# dsky_md_4_01v.net
KiCad netlist of a schematic drawn in EAGLE
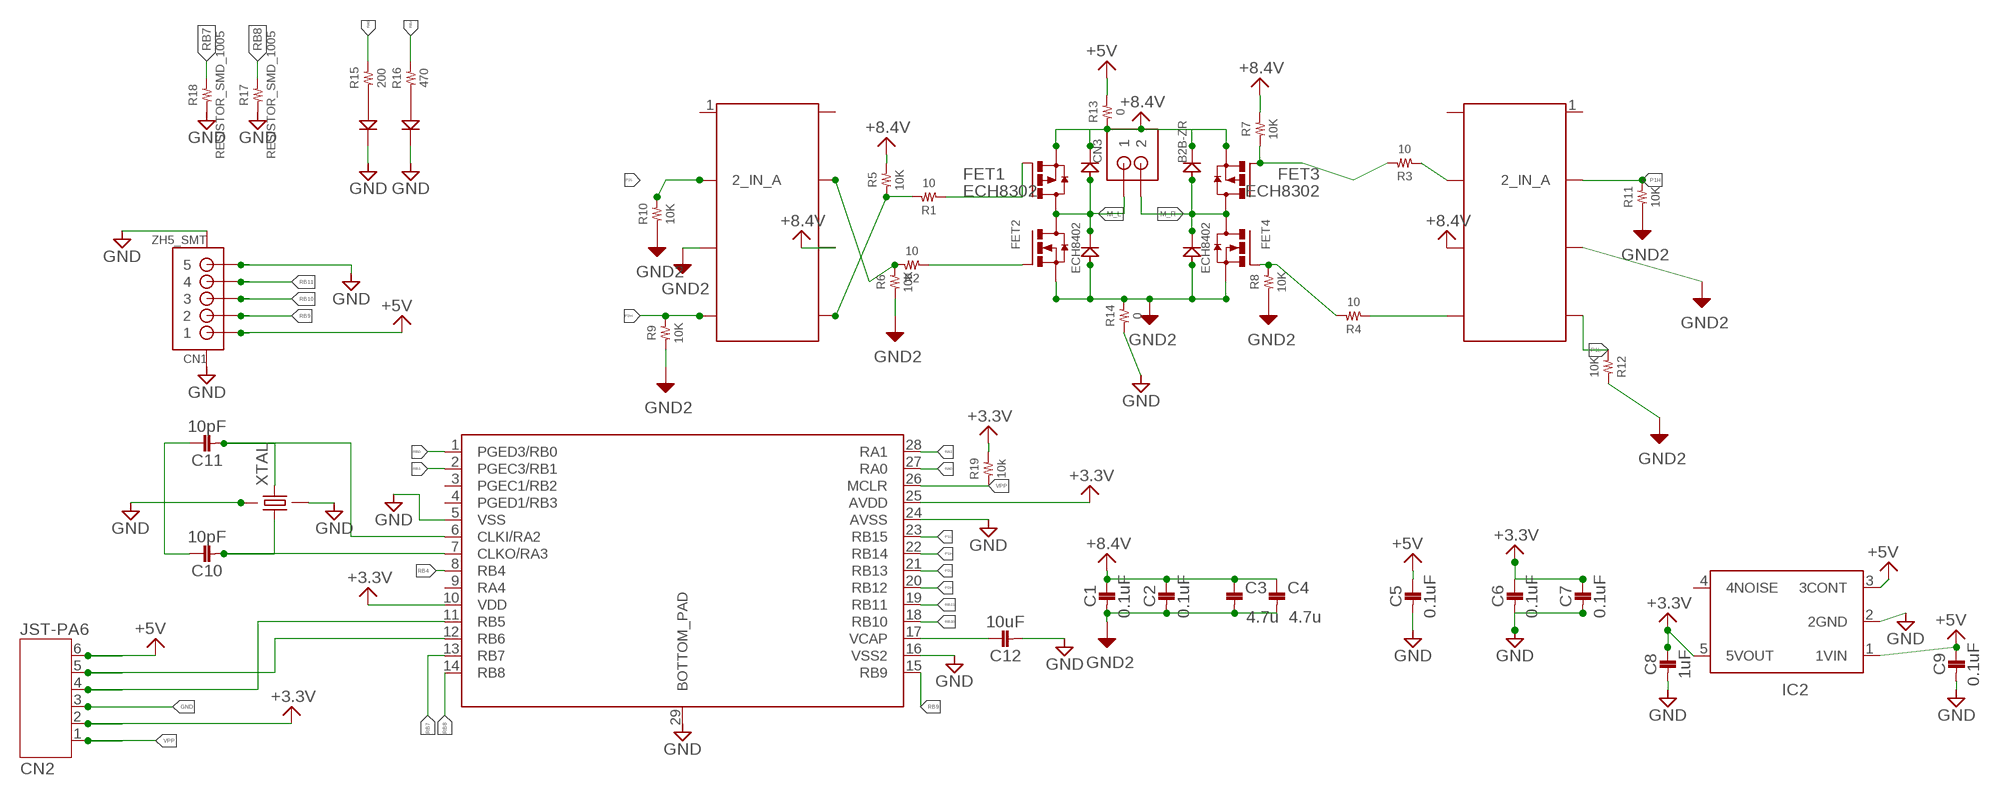
[diagram p0: schematic, sheet 1]

(export (version "E")
  (design (tool "Eeschema 10.0.6"))
  (components
    (comp (ref "C1")
      (value "0.1uF")
      (footprint "eagle-import:1608")
      (libsource (lib "eagle-import") (part "1608"))
    )
    (comp (ref "C2")
      (value "0.1uF")
      (footprint "eagle-import:1608")
      (libsource (lib "eagle-import") (part "1608"))
    )
    (comp (ref "C3")
      (value "4.7u")
      (footprint "eagle-import:2012")
      (libsource (lib "eagle-import") (part "2012"))
    )
    (comp (ref "C4")
      (value "4.7u")
      (footprint "eagle-import:2012")
      (libsource (lib "eagle-import") (part "2012"))
    )
    (comp (ref "C5")
      (value "0.1uF")
      (footprint "eagle-import:1608")
      (libsource (lib "eagle-import") (part "1608"))
    )
    (comp (ref "C6")
      (value "0.1uF")
      (footprint "eagle-import:1608")
      (libsource (lib "eagle-import") (part "1608"))
    )
    (comp (ref "C7")
      (value "0.1uF")
      (footprint "eagle-import:1608")
      (libsource (lib "eagle-import") (part "1608"))
    )
    (comp (ref "C8")
      (value "1uF")
      (footprint "eagle-import:1608")
      (libsource (lib "eagle-import") (part "1608"))
    )
    (comp (ref "C9")
      (value "0.1uF")
      (footprint "eagle-import:1608")
      (libsource (lib "eagle-import") (part "1608"))
    )
    (comp (ref "C10")
      (value "10pF")
      (footprint "eagle-import:1608")
      (libsource (lib "eagle-import") (part "1608"))
    )
    (comp (ref "C11")
      (value "10pF")
      (footprint "eagle-import:1608")
      (libsource (lib "eagle-import") (part "1608"))
    )
    (comp (ref "C12")
      (value "10uF")
      (footprint "eagle-import:1608")
      (libsource (lib "eagle-import") (part "1608"))
    )
    (comp (ref "CN1")
      (value "ZH5_SMT")
      (footprint "eagle-import:ZH5_SMT")
      (libsource (lib "eagle-import") (part "ZH5_SMT"))
    )
    (comp (ref "CN2")
      (value "JST-PA6")
      (footprint "eagle-import:JST-PA6")
      (libsource (lib "eagle-import") (part "JST-PA6"))
    )
    (comp (ref "CN3")
      (value "B2B-ZR")
      (footprint "eagle-import:B2B-ZR")
      (libsource (lib "eagle-import") (part "B2B-ZR"))
    )
    (comp (ref "D1")
      (value "SS2040")
      (footprint "eagle-import:SOD-123FL")
      (libsource (lib "eagle-import") (part "SS2040"))
    )
    (comp (ref "D2")
      (value "SS2040")
      (footprint "eagle-import:SOD-123FL")
      (libsource (lib "eagle-import") (part "SS2040"))
    )
    (comp (ref "D3")
      (value "SS2040")
      (footprint "eagle-import:SOD-123FL")
      (libsource (lib "eagle-import") (part "SS2040"))
    )
    (comp (ref "D4")
      (value "SS2040")
      (footprint "eagle-import:SOD-123FL")
      (libsource (lib "eagle-import") (part "SS2040"))
    )
    (comp (ref "FET1")
      (value "ECH8302")
      (footprint "eagle-import:ECH8")
      (libsource (lib "eagle-import") (part "ECH83"))
    )
    (comp (ref "FET2")
      (value "ECH8402")
      (footprint "eagle-import:ECH8")
      (libsource (lib "eagle-import") (part "ECH84"))
    )
    (comp (ref "FET3")
      (value "ECH8302")
      (footprint "eagle-import:ECH8")
      (libsource (lib "eagle-import") (part "ECH83"))
    )
    (comp (ref "FET4")
      (value "ECH8402")
      (footprint "eagle-import:ECH8")
      (libsource (lib "eagle-import") (part "ECH84"))
    )
    (comp (ref "IC1")
      (value "DSPIC33EP32MC202")
      (footprint "eagle-import:QFN-S28_6X6MC")
      (libsource (lib "eagle-import") (part "DSPIC33EP32MC202"))
    )
    (comp (ref "IC2")
      (value "NJM2866F33")
      (footprint "eagle-import:SSOP5-P-0.95")
      (libsource (lib "eagle-import") (part "TAR5SB"))
    )
    (comp (ref "IC3")
      (value "TC1427COA")
      (footprint "eagle-import:SOIC8")
      (libsource (lib "eagle-import") (part "TC1427COA"))
    )
    (comp (ref "IC4")
      (value "TC1427COA")
      (footprint "eagle-import:SOIC8")
      (libsource (lib "eagle-import") (part "TC1427COA"))
    )
    (comp (ref "LED1")
      (value "1608")
      (footprint "eagle-import:1608")
      (libsource (lib "eagle-import") (part "10_LED_1608"))
    )
    (comp (ref "LED2")
      (value "1608")
      (footprint "eagle-import:1608")
      (libsource (lib "eagle-import") (part "10_LED_1608"))
    )
    (comp (ref "R1")
      (value "10")
      (footprint "eagle-import:1608")
      (libsource (lib "eagle-import") (part "RESISTOR__SMD"))
    )
    (comp (ref "R2")
      (value "10")
      (footprint "eagle-import:1608")
      (libsource (lib "eagle-import") (part "RESISTOR__SMD"))
    )
    (comp (ref "R3")
      (value "10")
      (footprint "eagle-import:1608")
      (libsource (lib "eagle-import") (part "RESISTOR__SMD"))
    )
    (comp (ref "R4")
      (value "10")
      (footprint "eagle-import:1608")
      (libsource (lib "eagle-import") (part "RESISTOR__SMD"))
    )
    (comp (ref "R5")
      (value "10K")
      (footprint "eagle-import:1608")
      (libsource (lib "eagle-import") (part "RESISTOR__SMD"))
    )
    (comp (ref "R6")
      (value "10K")
      (footprint "eagle-import:1608")
      (libsource (lib "eagle-import") (part "RESISTOR__SMD"))
    )
    (comp (ref "R7")
      (value "10K")
      (footprint "eagle-import:1608")
      (libsource (lib "eagle-import") (part "RESISTOR__SMD"))
    )
    (comp (ref "R8")
      (value "10K")
      (footprint "eagle-import:1608")
      (libsource (lib "eagle-import") (part "RESISTOR__SMD"))
    )
    (comp (ref "R9")
      (value "10K")
      (footprint "eagle-import:1608")
      (libsource (lib "eagle-import") (part "RESISTOR__SMD"))
    )
    (comp (ref "R10")
      (value "10K")
      (footprint "eagle-import:1608")
      (libsource (lib "eagle-import") (part "RESISTOR__SMD"))
    )
    (comp (ref "R11")
      (value "10K")
      (footprint "eagle-import:1608")
      (libsource (lib "eagle-import") (part "RESISTOR__SMD"))
    )
    (comp (ref "R12")
      (value "10K")
      (footprint "eagle-import:1608")
      (libsource (lib "eagle-import") (part "RESISTOR__SMD"))
    )
    (comp (ref "R13")
      (value "0")
      (footprint "eagle-import:1608")
      (libsource (lib "eagle-import") (part "RESISTOR__SMD"))
    )
    (comp (ref "R14")
      (value "0")
      (footprint "eagle-import:1608")
      (libsource (lib "eagle-import") (part "RESISTOR__SMD"))
    )
    (comp (ref "R15")
      (value "200")
      (footprint "eagle-import:1608")
      (libsource (lib "eagle-import") (part "RESISTOR__SMD"))
    )
    (comp (ref "R16")
      (value "470")
      (footprint "eagle-import:1608")
      (libsource (lib "eagle-import") (part "RESISTOR__SMD"))
    )
    (comp (ref "R17")
      (value "RESISTOR_SMD_1005")
      (footprint "eagle-import:1005")
      (libsource (lib "eagle-import") (part "RESISTOR_SMD_1005"))
    )
    (comp (ref "R18")
      (value "RESISTOR_SMD_1005")
      (footprint "eagle-import:1005")
      (libsource (lib "eagle-import") (part "RESISTOR_SMD_1005"))
    )
    (comp (ref "R19")
      (value "10k")
      (footprint "eagle-import:1608")
      (libsource (lib "eagle-import") (part "RESISTOR__SMD"))
    )
    (comp (ref "XTAL")
      (value "X22")
      (footprint "eagle-import:SMD_X22")
      (libsource (lib "eagle-import") (part "X22"))
    )
  )
  (nets
    (net (code "1") (name "+3.3V") (class "Default")
      (node (ref "C6") (pin "P$1") (pinfunction "1_P$1") (pintype "passive"))
      (node (ref "C7") (pin "P$1") (pinfunction "1_P$1") (pintype "passive"))
      (node (ref "C8") (pin "P$1") (pinfunction "1_P$1") (pintype "passive"))
      (node (ref "CN2") (pin "2") (pinfunction "2_2") (pintype "passive"))
      (node (ref "IC1") (pin "10") (pinfunction "VDD_10") (pintype "bidirectional"))
      (node (ref "IC1") (pin "25") (pinfunction "AVDD_25") (pintype "bidirectional"))
      (node (ref "IC2") (pin "5") (pinfunction "5VOUT_5") (pintype "bidirectional"))
      (node (ref "R19") (pin "2") (pinfunction "P$2_2") (pintype "passive"))
    )
    (net (code "2") (name "+5V") (class "Default")
      (node (ref "C5") (pin "P$1") (pinfunction "1_P$1") (pintype "passive"))
      (node (ref "C9") (pin "P$1") (pinfunction "1_P$1") (pintype "passive"))
      (node (ref "CN1") (pin "P1") (pinfunction "1_P1") (pintype "bidirectional"))
      (node (ref "CN2") (pin "6") (pinfunction "6_6") (pintype "passive"))
      (node (ref "IC2") (pin "1") (pinfunction "1VIN_1") (pintype "bidirectional"))
      (node (ref "IC2") (pin "3") (pinfunction "3CONT_3") (pintype "bidirectional"))
      (node (ref "R13") (pin "2") (pinfunction "P$2_2") (pintype "passive"))
    )
    (net (code "3") (name "+8.4V") (class "Default")
      (node (ref "C1") (pin "P$1") (pinfunction "1_P$1") (pintype "passive"))
      (node (ref "C2") (pin "P$1") (pinfunction "1_P$1") (pintype "passive"))
      (node (ref "C3") (pin "1") (pinfunction "1_1") (pintype "passive"))
      (node (ref "C4") (pin "1") (pinfunction "1_1") (pintype "passive"))
      (node (ref "D1") (pin "2") (pinfunction "PK_2") (pintype "bidirectional"))
      (node (ref "D3") (pin "2") (pinfunction "PK_2") (pintype "bidirectional"))
      (node (ref "FET1") (pin "1") (pinfunction "S_1") (pintype "passive"))
      (node (ref "FET1") (pin "2") (pinfunction "S_2") (pintype "passive"))
      (node (ref "FET1") (pin "3") (pinfunction "S_3") (pintype "passive"))
      (node (ref "FET3") (pin "1") (pinfunction "S_1") (pintype "passive"))
      (node (ref "FET3") (pin "2") (pinfunction "S_2") (pintype "passive"))
      (node (ref "FET3") (pin "3") (pinfunction "S_3") (pintype "passive"))
      (node (ref "IC3") (pin "6") (pinfunction "6_VDD_6") (pintype "bidirectional"))
      (node (ref "IC4") (pin "6") (pinfunction "6_VDD_6") (pintype "bidirectional"))
      (node (ref "R13") (pin "1") (pinfunction "P$1_1") (pintype "passive"))
      (node (ref "R5") (pin "2") (pinfunction "P$2_2") (pintype "passive"))
      (node (ref "R7") (pin "2") (pinfunction "P$2_2") (pintype "passive"))
    )
    (net (code "4") (name "GND") (class "Default")
      (node (ref "C10") (pin "P$1") (pinfunction "1_P$1") (pintype "passive"))
      (node (ref "C11") (pin "P$1") (pinfunction "1_P$1") (pintype "passive"))
      (node (ref "C12") (pin "P$2") (pinfunction "2_P$2") (pintype "passive"))
      (node (ref "C5") (pin "P$2") (pinfunction "2_P$2") (pintype "passive"))
      (node (ref "C6") (pin "P$2") (pinfunction "2_P$2") (pintype "passive"))
      (node (ref "C7") (pin "P$2") (pinfunction "2_P$2") (pintype "passive"))
      (node (ref "C8") (pin "P$2") (pinfunction "2_P$2") (pintype "passive"))
      (node (ref "C9") (pin "P$2") (pinfunction "2_P$2") (pintype "passive"))
      (node (ref "CN1") (pin "G1") (pinfunction "G_L_G1") (pintype "bidirectional"))
      (node (ref "CN1") (pin "G2") (pinfunction "G_R_G2") (pintype "bidirectional"))
      (node (ref "CN1") (pin "P5") (pinfunction "5_P5") (pintype "bidirectional"))
      (node (ref "CN2") (pin "3") (pinfunction "3_3") (pintype "passive"))
      (node (ref "IC1") (pin "16") (pinfunction "VSS2_16") (pintype "power_in"))
      (node (ref "IC1") (pin "24") (pinfunction "AVSS_24") (pintype "bidirectional"))
      (node (ref "IC1") (pin "29") (pinfunction "BOTTOM_PAD_29") (pintype "bidirectional"))
      (node (ref "IC1") (pin "5") (pinfunction "VSS_5") (pintype "power_in"))
      (node (ref "IC2") (pin "2") (pinfunction "2GND_2") (pintype "bidirectional"))
      (node (ref "LED1") (pin "2") (pinfunction "K_2") (pintype "bidirectional"))
      (node (ref "LED2") (pin "2") (pinfunction "K_2") (pintype "bidirectional"))
      (node (ref "R14") (pin "1") (pinfunction "P$1_1") (pintype "passive"))
      (node (ref "R17") (pin "1") (pinfunction "P$1_1") (pintype "passive"))
      (node (ref "R18") (pin "1") (pinfunction "P$1_1") (pintype "passive"))
      (node (ref "XTAL") (pin "2") (pinfunction "2_2") (pintype "bidirectional"))
      (node (ref "XTAL") (pin "4") (pinfunction "4_4") (pintype "bidirectional"))
    )
    (net (code "5") (name "GND2") (class "Default")
      (node (ref "C1") (pin "P$2") (pinfunction "2_P$2") (pintype "passive"))
      (node (ref "C2") (pin "P$2") (pinfunction "2_P$2") (pintype "passive"))
      (node (ref "C3") (pin "2") (pinfunction "2_2") (pintype "passive"))
      (node (ref "C4") (pin "2") (pinfunction "2_2") (pintype "passive"))
      (node (ref "D2") (pin "1") (pinfunction "PA_1") (pintype "bidirectional"))
      (node (ref "D4") (pin "1") (pinfunction "PA_1") (pintype "bidirectional"))
      (node (ref "FET2") (pin "1") (pinfunction "S_1") (pintype "passive"))
      (node (ref "FET2") (pin "2") (pinfunction "S_2") (pintype "passive"))
      (node (ref "FET2") (pin "3") (pinfunction "S_3") (pintype "passive"))
      (node (ref "FET4") (pin "1") (pinfunction "S_1") (pintype "passive"))
      (node (ref "FET4") (pin "2") (pinfunction "S_2") (pintype "passive"))
      (node (ref "FET4") (pin "3") (pinfunction "S_3") (pintype "passive"))
      (node (ref "IC3") (pin "3") (pinfunction "3_GND_3") (pintype "bidirectional"))
      (node (ref "IC4") (pin "3") (pinfunction "3_GND_3") (pintype "bidirectional"))
      (node (ref "R10") (pin "1") (pinfunction "P$1_1") (pintype "passive"))
      (node (ref "R11") (pin "1") (pinfunction "P$1_1") (pintype "passive"))
      (node (ref "R12") (pin "2") (pinfunction "P$2_2") (pintype "passive"))
      (node (ref "R14") (pin "2") (pinfunction "P$2_2") (pintype "passive"))
      (node (ref "R6") (pin "1") (pinfunction "P$1_1") (pintype "passive"))
      (node (ref "R8") (pin "1") (pinfunction "P$1_1") (pintype "passive"))
      (node (ref "R9") (pin "1") (pinfunction "P$1_1") (pintype "passive"))
    )
    (net (code "6") (name "M_L") (class "Default")
      (node (ref "CN3") (pin "1") (pinfunction "1_1") (pintype "bidirectional"))
      (node (ref "D1") (pin "1") (pinfunction "PA_1") (pintype "bidirectional"))
      (node (ref "D2") (pin "2") (pinfunction "PK_2") (pintype "bidirectional"))
      (node (ref "FET1") (pin "5") (pinfunction "D_5") (pintype "passive"))
      (node (ref "FET1") (pin "6") (pinfunction "D_6") (pintype "passive"))
      (node (ref "FET1") (pin "7") (pinfunction "D_7") (pintype "passive"))
      (node (ref "FET1") (pin "8") (pinfunction "D_8") (pintype "passive"))
      (node (ref "FET2") (pin "5") (pinfunction "D_5") (pintype "passive"))
      (node (ref "FET2") (pin "6") (pinfunction "D_6") (pintype "passive"))
      (node (ref "FET2") (pin "7") (pinfunction "D_7") (pintype "passive"))
      (node (ref "FET2") (pin "8") (pinfunction "D_8") (pintype "passive"))
    )
    (net (code "7") (name "M_R") (class "Default")
      (node (ref "CN3") (pin "2") (pinfunction "2_2") (pintype "bidirectional"))
      (node (ref "D3") (pin "1") (pinfunction "PA_1") (pintype "bidirectional"))
      (node (ref "D4") (pin "2") (pinfunction "PK_2") (pintype "bidirectional"))
      (node (ref "FET3") (pin "5") (pinfunction "D_5") (pintype "passive"))
      (node (ref "FET3") (pin "6") (pinfunction "D_6") (pintype "passive"))
      (node (ref "FET3") (pin "7") (pinfunction "D_7") (pintype "passive"))
      (node (ref "FET3") (pin "8") (pinfunction "D_8") (pintype "passive"))
      (node (ref "FET4") (pin "5") (pinfunction "D_5") (pintype "passive"))
      (node (ref "FET4") (pin "6") (pinfunction "D_6") (pintype "passive"))
      (node (ref "FET4") (pin "7") (pinfunction "D_7") (pintype "passive"))
      (node (ref "FET4") (pin "8") (pinfunction "D_8") (pintype "passive"))
    )
    (net (code "8") (name "Net-(C10-2)") (class "Default")
      (node (ref "C10") (pin "P$2") (pinfunction "2_P$2") (pintype "passive"))
      (node (ref "IC1") (pin "7") (pinfunction "CLKO/RA3_7") (pintype "bidirectional"))
      (node (ref "XTAL") (pin "1") (pinfunction "1_1") (pintype "passive"))
    )
    (net (code "9") (name "Net-(C11-2)") (class "Default")
      (node (ref "C11") (pin "P$2") (pinfunction "2_P$2") (pintype "passive"))
      (node (ref "IC1") (pin "6") (pinfunction "CLKI/RA2_6") (pintype "bidirectional"))
      (node (ref "XTAL") (pin "3") (pinfunction "3_3") (pintype "passive"))
    )
    (net (code "10") (name "Net-(C12-1)") (class "Default")
      (node (ref "C12") (pin "P$1") (pinfunction "1_P$1") (pintype "passive"))
      (node (ref "IC1") (pin "17") (pinfunction "VCAP_17") (pintype "bidirectional"))
    )
    (net (code "11") (name "Net-(FET1-G)") (class "Default")
      (node (ref "FET1") (pin "4") (pinfunction "G_4") (pintype "passive"))
      (node (ref "R1") (pin "1") (pinfunction "P$1_1") (pintype "passive"))
    )
    (net (code "12") (name "Net-(FET2-G)") (class "Default")
      (node (ref "FET2") (pin "4") (pinfunction "G_4") (pintype "passive"))
      (node (ref "R2") (pin "1") (pinfunction "P$1_1") (pintype "passive"))
    )
    (net (code "13") (name "Net-(FET3-G)") (class "Default")
      (node (ref "FET3") (pin "4") (pinfunction "G_4") (pintype "passive"))
      (node (ref "R3") (pin "2") (pinfunction "P$2_2") (pintype "passive"))
      (node (ref "R7") (pin "1") (pinfunction "P$1_1") (pintype "passive"))
    )
    (net (code "14") (name "Net-(FET4-G)") (class "Default")
      (node (ref "FET4") (pin "4") (pinfunction "G_4") (pintype "passive"))
      (node (ref "R4") (pin "2") (pinfunction "P$2_2") (pintype "passive"))
      (node (ref "R8") (pin "2") (pinfunction "P$2_2") (pintype "passive"))
    )
    (net (code "15") (name "Net-(IC1-RB5)") (class "Default")
      (node (ref "CN2") (pin "4") (pinfunction "4_4") (pintype "passive"))
      (node (ref "IC1") (pin "11") (pinfunction "RB5_11") (pintype "bidirectional"))
    )
    (net (code "16") (name "Net-(IC1-RB6)") (class "Default")
      (node (ref "CN2") (pin "5") (pinfunction "5_5") (pintype "passive"))
      (node (ref "IC1") (pin "12") (pinfunction "RB6_12") (pintype "bidirectional"))
    )
    (net (code "17") (name "Net-(IC3-5_OUT_B)") (class "Default")
      (node (ref "IC3") (pin "5") (pinfunction "5_OUT_B_5") (pintype "bidirectional"))
      (node (ref "R1") (pin "2") (pinfunction "P$2_2") (pintype "passive"))
      (node (ref "R5") (pin "1") (pinfunction "P$1_1") (pintype "passive"))
    )
    (net (code "18") (name "Net-(IC3-7_OUT_A)") (class "Default")
      (node (ref "IC3") (pin "7") (pinfunction "7_OUT_A_7") (pintype "bidirectional"))
      (node (ref "R2") (pin "2") (pinfunction "P$2_2") (pintype "passive"))
      (node (ref "R6") (pin "2") (pinfunction "P$2_2") (pintype "passive"))
    )
    (net (code "19") (name "Net-(IC4-5_OUT_B)") (class "Default")
      (node (ref "IC4") (pin "5") (pinfunction "5_OUT_B_5") (pintype "bidirectional"))
      (node (ref "R4") (pin "1") (pinfunction "P$1_1") (pintype "passive"))
    )
    (net (code "20") (name "Net-(IC4-7_OUT_A)") (class "Default")
      (node (ref "IC4") (pin "7") (pinfunction "7_OUT_A_7") (pintype "bidirectional"))
      (node (ref "R3") (pin "1") (pinfunction "P$1_1") (pintype "passive"))
    )
    (net (code "21") (name "Net-(LED1-A)") (class "Default")
      (node (ref "LED1") (pin "1") (pinfunction "A_1") (pintype "bidirectional"))
      (node (ref "R15") (pin "1") (pinfunction "P$1_1") (pintype "passive"))
    )
    (net (code "22") (name "Net-(LED2-A)") (class "Default")
      (node (ref "LED2") (pin "1") (pinfunction "A_1") (pintype "bidirectional"))
      (node (ref "R16") (pin "1") (pinfunction "P$1_1") (pintype "passive"))
    )
    (net (code "23") (name "P1H") (class "Default")
      (node (ref "IC1") (pin "22") (pinfunction "RB14_22") (pintype "bidirectional"))
      (node (ref "IC4") (pin "2") (pinfunction "2_IN_A_2") (pintype "bidirectional"))
      (node (ref "R11") (pin "2") (pinfunction "P$2_2") (pintype "passive"))
    )
    (net (code "24") (name "P1L") (class "Default")
      (node (ref "IC1") (pin "23") (pinfunction "RB15_23") (pintype "bidirectional"))
      (node (ref "IC4") (pin "4") (pinfunction "4_IN_B_4") (pintype "bidirectional"))
      (node (ref "R12") (pin "1") (pinfunction "P$1_1") (pintype "passive"))
    )
    (net (code "25") (name "P2H") (class "Default")
      (node (ref "IC1") (pin "20") (pinfunction "RB12_20") (pintype "bidirectional"))
      (node (ref "IC3") (pin "4") (pinfunction "4_IN_B_4") (pintype "bidirectional"))
      (node (ref "R9") (pin "2") (pinfunction "P$2_2") (pintype "passive"))
    )
    (net (code "26") (name "P2L") (class "Default")
      (node (ref "IC1") (pin "21") (pinfunction "RB13_21") (pintype "bidirectional"))
      (node (ref "IC3") (pin "2") (pinfunction "2_IN_A_2") (pintype "bidirectional"))
      (node (ref "R10") (pin "2") (pinfunction "P$2_2") (pintype "passive"))
    )
    (net (code "27") (name "RA0") (class "Default")
      (node (ref "IC1") (pin "27") (pinfunction "RA0_27") (pintype "bidirectional"))
      (node (ref "R15") (pin "2") (pinfunction "P$2_2") (pintype "passive"))
    )
    (net (code "28") (name "RA1") (class "Default")
      (node (ref "IC1") (pin "28") (pinfunction "RA1_28") (pintype "bidirectional"))
    )
    (net (code "29") (name "RB0") (class "Default")
      (node (ref "IC1") (pin "1") (pinfunction "PGED3/RB0_1") (pintype "bidirectional"))
    )
    (net (code "30") (name "RB1") (class "Default")
      (node (ref "IC1") (pin "2") (pinfunction "PGEC3/RB1_2") (pintype "bidirectional"))
    )
    (net (code "31") (name "RB4") (class "Default")
      (node (ref "IC1") (pin "8") (pinfunction "RB4_8") (pintype "bidirectional"))
      (node (ref "R16") (pin "2") (pinfunction "P$2_2") (pintype "passive"))
    )
    (net (code "32") (name "RB7") (class "Default")
      (node (ref "IC1") (pin "13") (pinfunction "RB7_13") (pintype "bidirectional"))
      (node (ref "R18") (pin "2") (pinfunction "P$2_2") (pintype "passive"))
    )
    (net (code "33") (name "RB8") (class "Default")
      (node (ref "IC1") (pin "14") (pinfunction "RB8_14") (pintype "bidirectional"))
      (node (ref "R17") (pin "2") (pinfunction "P$2_2") (pintype "passive"))
    )
    (net (code "34") (name "RB9") (class "Default")
      (node (ref "CN1") (pin "P2") (pinfunction "2_P2") (pintype "bidirectional"))
      (node (ref "IC1") (pin "15") (pinfunction "RB9_15") (pintype "bidirectional"))
    )
    (net (code "35") (name "RB10") (class "Default")
      (node (ref "CN1") (pin "P3") (pinfunction "3_P3") (pintype "bidirectional"))
      (node (ref "IC1") (pin "18") (pinfunction "RB10_18") (pintype "bidirectional"))
    )
    (net (code "36") (name "RB11") (class "Default")
      (node (ref "CN1") (pin "P4") (pinfunction "4_P4") (pintype "bidirectional"))
      (node (ref "IC1") (pin "19") (pinfunction "RB11_19") (pintype "bidirectional"))
    )
    (net (code "37") (name "VPP") (class "Default")
      (node (ref "CN2") (pin "1") (pinfunction "1_1") (pintype "passive"))
      (node (ref "IC1") (pin "26") (pinfunction "MCLR_26") (pintype "bidirectional"))
      (node (ref "R19") (pin "1") (pinfunction "P$1_1") (pintype "passive"))
    )
    (net (code "38") (name "unconnected-(IC1-PGEC1{slash}RB2-Pad3)") (class "Default")
      (node (ref "IC1") (pin "3") (pinfunction "PGEC1/RB2_3") (pintype "bidirectional"))
    )
    (net (code "39") (name "unconnected-(IC1-PGED1{slash}RB3-Pad4)") (class "Default")
      (node (ref "IC1") (pin "4") (pinfunction "PGED1/RB3_4") (pintype "bidirectional"))
    )
    (net (code "40") (name "unconnected-(IC1-RA4-Pad9)") (class "Default")
      (node (ref "IC1") (pin "9") (pinfunction "RA4_9") (pintype "bidirectional"))
    )
    (net (code "41") (name "unconnected-(IC2-4NOISE-Pad4)") (class "Default")
      (node (ref "IC2") (pin "4") (pinfunction "4NOISE_4") (pintype "bidirectional"))
    )
    (net (code "42") (name "unconnected-(IC3-1_NC-Pad1)") (class "Default")
      (node (ref "IC3") (pin "1") (pinfunction "1_NC_1") (pintype "bidirectional"))
    )
    (net (code "43") (name "unconnected-(IC3-8_NC-Pad8)") (class "Default")
      (node (ref "IC3") (pin "8") (pinfunction "8_NC_8") (pintype "bidirectional"))
    )
    (net (code "44") (name "unconnected-(IC4-1_NC-Pad1)") (class "Default")
      (node (ref "IC4") (pin "1") (pinfunction "1_NC_1") (pintype "bidirectional"))
    )
    (net (code "45") (name "unconnected-(IC4-8_NC-Pad8)") (class "Default")
      (node (ref "IC4") (pin "8") (pinfunction "8_NC_8") (pintype "bidirectional"))
    )
  )
)
